# battery_interface.net
KiCad netlist of a schematic drawn in Altium Designer
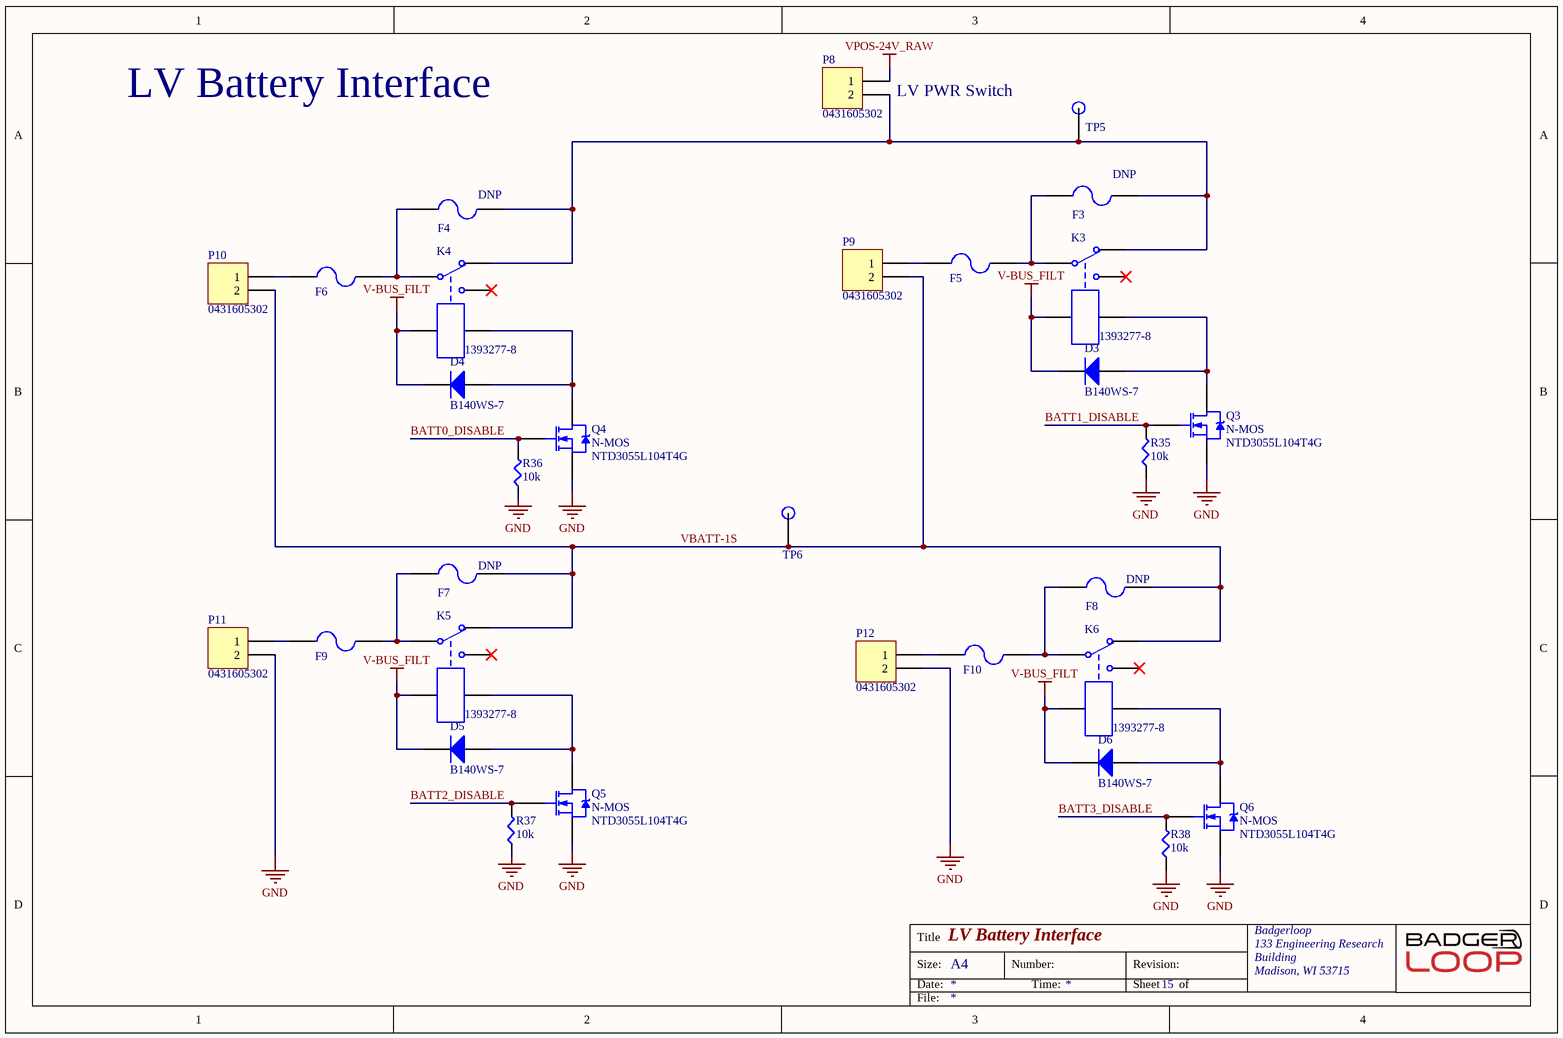
[diagram p0: battery_interface.SchDoc]

(export (version "E")
  (design (tool "Eeschema 10.0.6"))
  (components
    (comp (ref "D3")
      (value "B140WS-7")
      (footprint "SODFL250X110-2N")
      (description "Diode Schottky 40V 1A 2-Pin SOD-323 T/R")
      (fields (field (name "MANUFACTURER") "Diodes"))
      (libsource (lib "misc") (part "B140WS-7"))
    )
    (comp (ref "D4")
      (value "B140WS-7")
      (footprint "SODFL250X110-2N")
      (description "Diode Schottky 40V 1A 2-Pin SOD-323 T/R")
      (fields (field (name "MANUFACTURER") "Diodes"))
      (libsource (lib "misc") (part "B140WS-7"))
    )
    (comp (ref "D5")
      (value "B140WS-7")
      (footprint "SODFL250X110-2N")
      (description "Diode Schottky 40V 1A 2-Pin SOD-323 T/R")
      (fields (field (name "MANUFACTURER") "Diodes"))
      (libsource (lib "misc") (part "B140WS-7"))
    )
    (comp (ref "D6")
      (value "B140WS-7")
      (footprint "SODFL250X110-2N")
      (description "Diode Schottky 40V 1A 2-Pin SOD-323 T/R")
      (fields (field (name "MANUFACTURER") "Diodes"))
      (libsource (lib "misc") (part "B140WS-7"))
    )
    (comp (ref "F3")
      (value "3568")
      (footprint "Fuse Holder 30A 500V 1 Circuit Blade Through Hole")
      (description "FUSE HOLDER MINI AUTO PC")
      (fields
        (field (name "MANUFACTURER") "Keystone Electronics")
        (field (name "VOLTAGE") "500V")
        (field (name "DNP") "DNP")
      )
      (libsource (lib "misc") (part "3568"))
    )
    (comp (ref "F4")
      (value "3568")
      (footprint "Fuse Holder 30A 500V 1 Circuit Blade Through Hole")
      (description "FUSE HOLDER MINI AUTO PC")
      (fields
        (field (name "MANUFACTURER") "Keystone Electronics")
        (field (name "VOLTAGE") "500V")
        (field (name "DNP") "DNP")
      )
      (libsource (lib "misc") (part "3568"))
    )
    (comp (ref "F5")
      (value "3568")
      (footprint "Fuse Holder 30A 500V 1 Circuit Blade Through Hole")
      (description "FUSE HOLDER MINI AUTO PC")
      (fields (field (name "MANUFACTURER") "Keystone Electronics") (field (name "VOLTAGE") "500V"))
      (libsource (lib "misc") (part "3568"))
    )
    (comp (ref "F6")
      (value "3568")
      (footprint "Fuse Holder 30A 500V 1 Circuit Blade Through Hole")
      (description "FUSE HOLDER MINI AUTO PC")
      (fields (field (name "MANUFACTURER") "Keystone Electronics") (field (name "VOLTAGE") "500V"))
      (libsource (lib "misc") (part "3568"))
    )
    (comp (ref "F7")
      (value "3568")
      (footprint "Fuse Holder 30A 500V 1 Circuit Blade Through Hole")
      (description "FUSE HOLDER MINI AUTO PC")
      (fields
        (field (name "MANUFACTURER") "Keystone Electronics")
        (field (name "VOLTAGE") "500V")
        (field (name "DNP") "DNP")
      )
      (libsource (lib "misc") (part "3568"))
    )
    (comp (ref "F8")
      (value "3568")
      (footprint "Fuse Holder 30A 500V 1 Circuit Blade Through Hole")
      (description "FUSE HOLDER MINI AUTO PC")
      (fields
        (field (name "MANUFACTURER") "Keystone Electronics")
        (field (name "VOLTAGE") "500V")
        (field (name "DNP") "DNP")
      )
      (libsource (lib "misc") (part "3568"))
    )
    (comp (ref "F9")
      (value "3568")
      (footprint "Fuse Holder 30A 500V 1 Circuit Blade Through Hole")
      (description "FUSE HOLDER MINI AUTO PC")
      (fields (field (name "MANUFACTURER") "Keystone Electronics") (field (name "VOLTAGE") "500V"))
      (libsource (lib "misc") (part "3568"))
    )
    (comp (ref "F10")
      (value "3568")
      (footprint "Fuse Holder 30A 500V 1 Circuit Blade Through Hole")
      (description "FUSE HOLDER MINI AUTO PC")
      (fields (field (name "MANUFACTURER") "Keystone Electronics") (field (name "VOLTAGE") "500V"))
      (libsource (lib "misc") (part "3568"))
    )
    (comp (ref "K3")
      (value "1393277-8")
      (footprint "RELAY AUTOMOTIVE SPDT 45A 24V - duplicate")
      (description "RELAY AUTOMOTIVE SPDT 45A 24V")
      (fields (field (name "MANUFACTURER") "TE Connectivity"))
      (libsource (lib "misc") (part "1393277-8"))
    )
    (comp (ref "K4")
      (value "1393277-8")
      (footprint "RELAY AUTOMOTIVE SPDT 45A 24V - duplicate")
      (description "RELAY AUTOMOTIVE SPDT 45A 24V")
      (fields (field (name "MANUFACTURER") "TE Connectivity"))
      (libsource (lib "misc") (part "1393277-8"))
    )
    (comp (ref "K5")
      (value "1393277-8")
      (footprint "RELAY AUTOMOTIVE SPDT 45A 24V - duplicate")
      (description "RELAY AUTOMOTIVE SPDT 45A 24V")
      (fields (field (name "MANUFACTURER") "TE Connectivity"))
      (libsource (lib "misc") (part "1393277-8"))
    )
    (comp (ref "K6")
      (value "1393277-8")
      (footprint "RELAY AUTOMOTIVE SPDT 45A 24V - duplicate")
      (description "RELAY AUTOMOTIVE SPDT 45A 24V")
      (fields (field (name "MANUFACTURER") "TE Connectivity"))
      (libsource (lib "misc") (part "1393277-8"))
    )
    (comp (ref "P8")
      (value "0431605302")
      (footprint "CONN HDR 2POS 7.50MM")
      (description "Conn Power HDR 2 POS 7.49mm Solder RA Thru-Hole 4 Terminal 1 Port Sabre™ Tray")
      (fields (field (name "MANUFACTURER") "Molex"))
      (libsource (lib "connector") (part "0431605302"))
    )
    (comp (ref "P9")
      (value "0431605302")
      (footprint "CONN HDR 2POS 7.50MM")
      (description "Conn Power HDR 2 POS 7.49mm Solder RA Thru-Hole 4 Terminal 1 Port Sabre™ Tray")
      (fields (field (name "MANUFACTURER") "Molex"))
      (libsource (lib "connector") (part "0431605302"))
    )
    (comp (ref "P10")
      (value "0431605302")
      (footprint "CONN HDR 2POS 7.50MM")
      (description "Conn Power HDR 2 POS 7.49mm Solder RA Thru-Hole 4 Terminal 1 Port Sabre™ Tray")
      (fields (field (name "MANUFACTURER") "Molex"))
      (libsource (lib "connector") (part "0431605302"))
    )
    (comp (ref "P11")
      (value "0431605302")
      (footprint "CONN HDR 2POS 7.50MM")
      (description "Conn Power HDR 2 POS 7.49mm Solder RA Thru-Hole 4 Terminal 1 Port Sabre™ Tray")
      (fields (field (name "MANUFACTURER") "Molex"))
      (libsource (lib "connector") (part "0431605302"))
    )
    (comp (ref "P12")
      (value "0431605302")
      (footprint "CONN HDR 2POS 7.50MM")
      (description "Conn Power HDR 2 POS 7.49mm Solder RA Thru-Hole 4 Terminal 1 Port Sabre™ Tray")
      (fields (field (name "MANUFACTURER") "Molex"))
      (libsource (lib "connector") (part "0431605302"))
    )
    (comp (ref "Q3")
      (value "N-MOS")
      (footprint "DPAK228P991X238-3N")
      (description "N-Channel Power MOSFET, 12 A, 60 V")
      (fields (field (name "MANUFACTURER") "ON SEMI") (field (name "MANUFACTURER P/N") "NTD3055L104T4G"))
      (libsource (lib "ic") (part "N-MOS"))
    )
    (comp (ref "Q4")
      (value "N-MOS")
      (footprint "DPAK228P991X238-3N")
      (description "N-Channel Power MOSFET, 12 A, 60 V")
      (fields (field (name "MANUFACTURER") "ON SEMI") (field (name "MANUFACTURER P/N") "NTD3055L104T4G"))
      (libsource (lib "ic") (part "N-MOS"))
    )
    (comp (ref "Q5")
      (value "N-MOS")
      (footprint "DPAK228P991X238-3N")
      (description "N-Channel Power MOSFET, 12 A, 60 V")
      (fields (field (name "MANUFACTURER") "ON SEMI") (field (name "MANUFACTURER P/N") "NTD3055L104T4G"))
      (libsource (lib "ic") (part "N-MOS"))
    )
    (comp (ref "Q6")
      (value "N-MOS")
      (footprint "DPAK228P991X238-3N")
      (description "N-Channel Power MOSFET, 12 A, 60 V")
      (fields (field (name "MANUFACTURER") "ON SEMI") (field (name "MANUFACTURER P/N") "NTD3055L104T4G"))
      (libsource (lib "ic") (part "N-MOS"))
    )
    (comp (ref "R35")
      (value "10k")
      (footprint "SMD-0805-RES")
      (description "RES SMD 10K OHM 5% 1/2W 0805")
      (fields (field (name "PART NUMBER") "ERJ-P06J103V") (field (name "DIGI-KEY PART NUMBER") "P10KADCT-ND"))
      (libsource (lib "resistors") (part "ERJ-P06J103V"))
    )
    (comp (ref "R36")
      (value "10k")
      (footprint "SMD-0805-RES")
      (description "RES SMD 10K OHM 5% 1/2W 0805")
      (fields (field (name "PART NUMBER") "ERJ-P06J103V") (field (name "DIGI-KEY PART NUMBER") "P10KADCT-ND"))
      (libsource (lib "resistors") (part "ERJ-P06J103V"))
    )
    (comp (ref "R37")
      (value "10k")
      (footprint "SMD-0805-RES")
      (description "RES SMD 10K OHM 5% 1/2W 0805")
      (fields (field (name "PART NUMBER") "ERJ-P06J103V") (field (name "DIGI-KEY PART NUMBER") "P10KADCT-ND"))
      (libsource (lib "resistors") (part "ERJ-P06J103V"))
    )
    (comp (ref "R38")
      (value "10k")
      (footprint "SMD-0805-RES")
      (description "RES SMD 10K OHM 5% 1/2W 0805")
      (fields (field (name "PART NUMBER") "ERJ-P06J103V") (field (name "DIGI-KEY PART NUMBER") "P10KADCT-ND"))
      (libsource (lib "resistors") (part "ERJ-P06J103V"))
    )
    (comp (ref "TP5")
      (value "TP")
      (footprint "Test Point")
      (description "SMD TEST POINT")
      (libsource (lib "misc") (part "TP"))
    )
    (comp (ref "TP6")
      (value "TP")
      (footprint "Test Point")
      (description "SMD TEST POINT")
      (libsource (lib "misc") (part "TP"))
    )
  )
  (nets
    (net (code "1") (name "/BATT0_DISABLE") (class "Default")
      (node (ref "Q4") (pin "1") (pinfunction "G_1") (pintype "passive"))
      (node (ref "R36") (pin "2") (pinfunction "2_2") (pintype "passive"))
    )
    (net (code "2") (name "/BATT1_DISABLE") (class "Default")
      (node (ref "Q3") (pin "1") (pinfunction "G_1") (pintype "passive"))
      (node (ref "R35") (pin "2") (pinfunction "2_2") (pintype "passive"))
    )
    (net (code "3") (name "/BATT2_DISABLE") (class "Default")
      (node (ref "Q5") (pin "1") (pinfunction "G_1") (pintype "passive"))
      (node (ref "R37") (pin "2") (pinfunction "2_2") (pintype "passive"))
    )
    (net (code "4") (name "/BATT3_DISABLE") (class "Default")
      (node (ref "Q6") (pin "1") (pinfunction "G_1") (pintype "passive"))
      (node (ref "R38") (pin "2") (pinfunction "2_2") (pintype "passive"))
    )
    (net (code "5") (name "/VBATT-1S") (class "Default")
      (node (ref "F7") (pin "2") (pinfunction "2_2") (pintype "passive"))
      (node (ref "F8") (pin "2") (pinfunction "2_2") (pintype "passive"))
      (node (ref "K5") (pin "3") (pinfunction "3_3") (pintype "passive"))
      (node (ref "K6") (pin "3") (pinfunction "3_3") (pintype "passive"))
      (node (ref "P10") (pin "2") (pinfunction "2_2") (pintype "passive"))
      (node (ref "P9") (pin "2") (pinfunction "2_2") (pintype "passive"))
      (node (ref "TP6") (pin "1") (pinfunction "1_1") (pintype "passive"))
    )
    (net (code "6") (name "GND") (class "Default")
      (node (ref "P11") (pin "2") (pinfunction "2_2") (pintype "passive"))
      (node (ref "P12") (pin "2") (pinfunction "2_2") (pintype "passive"))
      (node (ref "Q3") (pin "3") (pinfunction "S_3") (pintype "passive"))
      (node (ref "Q4") (pin "3") (pinfunction "S_3") (pintype "passive"))
      (node (ref "Q5") (pin "3") (pinfunction "S_3") (pintype "passive"))
      (node (ref "Q6") (pin "3") (pinfunction "S_3") (pintype "passive"))
      (node (ref "R35") (pin "1") (pinfunction "1_1") (pintype "passive"))
      (node (ref "R36") (pin "1") (pinfunction "1_1") (pintype "passive"))
      (node (ref "R37") (pin "1") (pinfunction "1_1") (pintype "passive"))
      (node (ref "R38") (pin "1") (pinfunction "1_1") (pintype "passive"))
    )
    (net (code "7") (name "Net-(D3-A)") (class "Default")
      (node (ref "D3") (pin "1") (pinfunction "A_1") (pintype "passive"))
      (node (ref "K3") (pin "2") (pinfunction "2_2") (pintype "passive"))
      (node (ref "Q3") (pin "4") (pinfunction "D_4") (pintype "passive"))
    )
    (net (code "8") (name "Net-(D4-A)") (class "Default")
      (node (ref "D4") (pin "1") (pinfunction "A_1") (pintype "passive"))
      (node (ref "K4") (pin "2") (pinfunction "2_2") (pintype "passive"))
      (node (ref "Q4") (pin "4") (pinfunction "D_4") (pintype "passive"))
    )
    (net (code "9") (name "Net-(D5-A)") (class "Default")
      (node (ref "D5") (pin "1") (pinfunction "A_1") (pintype "passive"))
      (node (ref "K5") (pin "2") (pinfunction "2_2") (pintype "passive"))
      (node (ref "Q5") (pin "4") (pinfunction "D_4") (pintype "passive"))
    )
    (net (code "10") (name "Net-(D6-A)") (class "Default")
      (node (ref "D6") (pin "1") (pinfunction "A_1") (pintype "passive"))
      (node (ref "K6") (pin "2") (pinfunction "2_2") (pintype "passive"))
      (node (ref "Q6") (pin "4") (pinfunction "D_4") (pintype "passive"))
    )
    (net (code "11") (name "Net-(F3-Pad1)") (class "Default")
      (node (ref "F3") (pin "1") (pinfunction "1_1") (pintype "passive"))
      (node (ref "F5") (pin "2") (pinfunction "2_2") (pintype "passive"))
      (node (ref "K3") (pin "4") (pinfunction "4_4") (pintype "passive"))
    )
    (net (code "12") (name "Net-(F3-Pad2)") (class "Default")
      (node (ref "F3") (pin "2") (pinfunction "2_2") (pintype "passive"))
      (node (ref "F4") (pin "2") (pinfunction "2_2") (pintype "passive"))
      (node (ref "K3") (pin "3") (pinfunction "3_3") (pintype "passive"))
      (node (ref "K4") (pin "3") (pinfunction "3_3") (pintype "passive"))
      (node (ref "P8") (pin "2") (pinfunction "2_2") (pintype "passive"))
      (node (ref "TP5") (pin "1") (pinfunction "1_1") (pintype "passive"))
    )
    (net (code "13") (name "Net-(F4-Pad1)") (class "Default")
      (node (ref "F4") (pin "1") (pinfunction "1_1") (pintype "passive"))
      (node (ref "F6") (pin "2") (pinfunction "2_2") (pintype "passive"))
      (node (ref "K4") (pin "4") (pinfunction "4_4") (pintype "passive"))
    )
    (net (code "14") (name "Net-(F5-Pad1)") (class "Default")
      (node (ref "F5") (pin "1") (pinfunction "1_1") (pintype "passive"))
      (node (ref "P9") (pin "1") (pinfunction "1_1") (pintype "passive"))
    )
    (net (code "15") (name "Net-(F6-Pad1)") (class "Default")
      (node (ref "F6") (pin "1") (pinfunction "1_1") (pintype "passive"))
      (node (ref "P10") (pin "1") (pinfunction "1_1") (pintype "passive"))
    )
    (net (code "16") (name "Net-(F7-Pad1)") (class "Default")
      (node (ref "F7") (pin "1") (pinfunction "1_1") (pintype "passive"))
      (node (ref "F9") (pin "2") (pinfunction "2_2") (pintype "passive"))
      (node (ref "K5") (pin "4") (pinfunction "4_4") (pintype "passive"))
    )
    (net (code "17") (name "Net-(F9-Pad1)") (class "Default")
      (node (ref "F9") (pin "1") (pinfunction "1_1") (pintype "passive"))
      (node (ref "P11") (pin "1") (pinfunction "1_1") (pintype "passive"))
    )
    (net (code "18") (name "Net-(F10-Pad1)") (class "Default")
      (node (ref "F10") (pin "1") (pinfunction "1_1") (pintype "passive"))
      (node (ref "P12") (pin "1") (pinfunction "1_1") (pintype "passive"))
    )
    (net (code "19") (name "Net-(F10-Pad2)") (class "Default")
      (node (ref "F10") (pin "2") (pinfunction "2_2") (pintype "passive"))
      (node (ref "F8") (pin "1") (pinfunction "1_1") (pintype "passive"))
      (node (ref "K6") (pin "4") (pinfunction "4_4") (pintype "passive"))
    )
    (net (code "20") (name "V-BUS_FILT") (class "Default")
      (node (ref "D3") (pin "2") (pinfunction "K_2") (pintype "passive"))
      (node (ref "D4") (pin "2") (pinfunction "K_2") (pintype "passive"))
      (node (ref "D5") (pin "2") (pinfunction "K_2") (pintype "passive"))
      (node (ref "D6") (pin "2") (pinfunction "K_2") (pintype "passive"))
      (node (ref "K3") (pin "1") (pinfunction "1_1") (pintype "passive"))
      (node (ref "K4") (pin "1") (pinfunction "1_1") (pintype "passive"))
      (node (ref "K5") (pin "1") (pinfunction "1_1") (pintype "passive"))
      (node (ref "K6") (pin "1") (pinfunction "1_1") (pintype "passive"))
    )
    (net (code "21") (name "VPOS-24V_RAW") (class "Default")
      (node (ref "P8") (pin "1") (pinfunction "1_1") (pintype "passive"))
    )
    (net (code "22") (name "unconnected-(K3-Pad5)") (class "Default")
      (node (ref "K3") (pin "5") (pinfunction "5_5") (pintype "passive+no_connect"))
    )
    (net (code "23") (name "unconnected-(K4-Pad5)") (class "Default")
      (node (ref "K4") (pin "5") (pinfunction "5_5") (pintype "passive+no_connect"))
    )
    (net (code "24") (name "unconnected-(K5-Pad5)") (class "Default")
      (node (ref "K5") (pin "5") (pinfunction "5_5") (pintype "passive+no_connect"))
    )
    (net (code "25") (name "unconnected-(K6-Pad5)") (class "Default")
      (node (ref "K6") (pin "5") (pinfunction "5_5") (pintype "passive+no_connect"))
    )
  )
)
